# Plaat.net
KiCad netlist of a schematic drawn in EAGLE
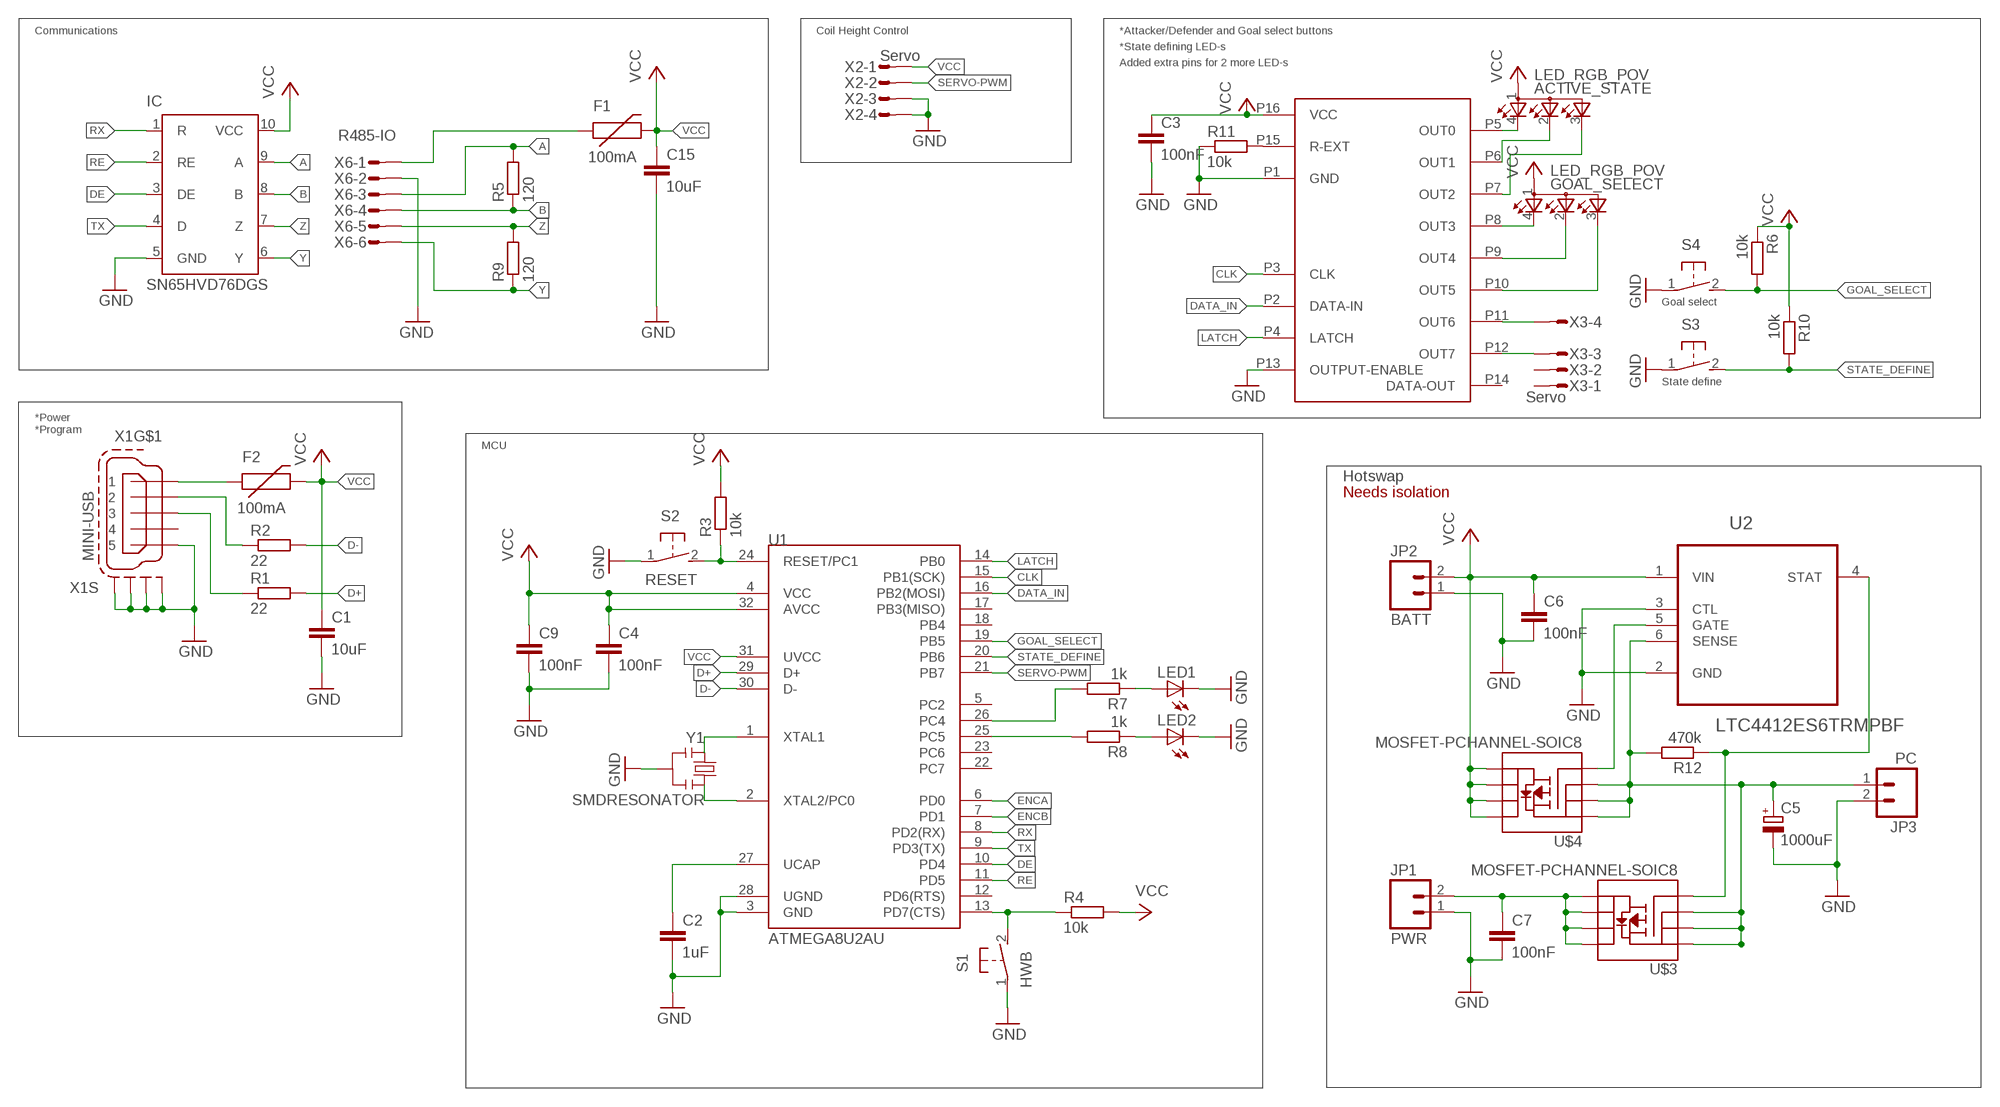
[diagram p0: schematic, sheet 1]

(export (version "E")
  (design (tool "Eeschema 10.0.6"))
  (components
    (comp (ref "ACTIVE_STATE")
      (value "LED_RGB_POV")
      (footprint "eagle-import:P-LCC-4-2")
      (libsource (lib "eagle-import") (part "LED_RGB_POV"))
    )
    (comp (ref "C1")
      (value "10uF")
      (footprint "eagle-import:C1206K")
      (libsource (lib "eagle-import") (part "C-EUC1206K"))
    )
    (comp (ref "C2")
      (value "1uF")
      (footprint "eagle-import:C0603K")
      (libsource (lib "eagle-import") (part "C-EUC0603K"))
    )
    (comp (ref "C3")
      (value "100nF")
      (footprint "eagle-import:C0603K")
      (libsource (lib "eagle-import") (part "C-EUC0603K"))
    )
    (comp (ref "C4")
      (value "100nF")
      (footprint "eagle-import:C0603K")
      (libsource (lib "eagle-import") (part "C-EUC0603K"))
    )
    (comp (ref "C5")
      (value "1000uF")
      (footprint "eagle-import:E3,5-8")
      (libsource (lib "eagle-import") (part "CPOL-EUE3.5-8"))
    )
    (comp (ref "C6")
      (value "100nF")
      (footprint "eagle-import:C0603K")
      (libsource (lib "eagle-import") (part "C-EUC0603K"))
    )
    (comp (ref "C7")
      (value "100nF")
      (footprint "eagle-import:C0603K")
      (libsource (lib "eagle-import") (part "C-EUC0603K"))
    )
    (comp (ref "C9")
      (value "100nF")
      (footprint "eagle-import:C0603K")
      (libsource (lib "eagle-import") (part "C-EUC0603K"))
    )
    (comp (ref "C15")
      (value "10uF")
      (footprint "eagle-import:C1206K")
      (libsource (lib "eagle-import") (part "C-EUC1206K"))
    )
    (comp (ref "F1")
      (value "100mA")
      (footprint "eagle-import:PTC-1206")
      (libsource (lib "eagle-import") (part "PTCSMD"))
    )
    (comp (ref "F2")
      (value "100mA")
      (footprint "eagle-import:PTC-1206")
      (libsource (lib "eagle-import") (part "PTCSMD"))
    )
    (comp (ref "GOAL_SELECT")
      (value "LED_RGB_POV")
      (footprint "eagle-import:P-LCC-4-2")
      (libsource (lib "eagle-import") (part "LED_RGB_POV"))
    )
    (comp (ref "JP1")
      (value "PWR")
      (footprint "eagle-import:SCREWTERMINAL-3.5MM-2")
      (libsource (lib "eagle-import") (part "M023.5MM"))
    )
    (comp (ref "JP2")
      (value "BATT")
      (footprint "eagle-import:SCREWTERMINAL-3.5MM-2")
      (libsource (lib "eagle-import") (part "M023.5MM"))
    )
    (comp (ref "JP3")
      (value "PC")
      (footprint "eagle-import:SCREWTERMINAL-3.5MM-2")
      (libsource (lib "eagle-import") (part "M023.5MM"))
    )
    (comp (ref "LED1")
      (value "LEDCHIP-LED0603")
      (footprint "eagle-import:CHIP-LED0603")
      (libsource (lib "eagle-import") (part "LEDCHIP-LED0603"))
    )
    (comp (ref "LED2")
      (value "LEDCHIP-LED0603")
      (footprint "eagle-import:CHIP-LED0603")
      (libsource (lib "eagle-import") (part "LEDCHIP-LED0603"))
    )
    (comp (ref "R1")
      (value "22")
      (footprint "eagle-import:R0603")
      (libsource (lib "eagle-import") (part "R-EU_R0603"))
    )
    (comp (ref "R2")
      (value "22")
      (footprint "eagle-import:R0603")
      (libsource (lib "eagle-import") (part "R-EU_R0603"))
    )
    (comp (ref "R3")
      (value "10k")
      (footprint "eagle-import:R0603")
      (libsource (lib "eagle-import") (part "R-EU_R0603"))
    )
    (comp (ref "R4")
      (value "10k")
      (footprint "eagle-import:R0603")
      (libsource (lib "eagle-import") (part "R-EU_R0603"))
    )
    (comp (ref "R5")
      (value "120")
      (footprint "eagle-import:R0603")
      (libsource (lib "eagle-import") (part "R-EU_R0603"))
    )
    (comp (ref "R6")
      (value "10k")
      (footprint "eagle-import:R0603")
      (libsource (lib "eagle-import") (part "R-EU_R0603"))
    )
    (comp (ref "R7")
      (value "1k")
      (footprint "eagle-import:R0603")
      (libsource (lib "eagle-import") (part "R-EU_R0603"))
    )
    (comp (ref "R8")
      (value "1k")
      (footprint "eagle-import:R0603")
      (libsource (lib "eagle-import") (part "R-EU_R0603"))
    )
    (comp (ref "R9")
      (value "120")
      (footprint "eagle-import:R0603")
      (libsource (lib "eagle-import") (part "R-EU_R0603"))
    )
    (comp (ref "R10")
      (value "10k")
      (footprint "eagle-import:R0603")
      (libsource (lib "eagle-import") (part "R-EU_R0603"))
    )
    (comp (ref "R11")
      (value "10k")
      (footprint "eagle-import:R0603")
      (libsource (lib "eagle-import") (part "R-EU_R0603"))
    )
    (comp (ref "R12")
      (value "470k")
      (footprint "eagle-import:R0603")
      (libsource (lib "eagle-import") (part "R-EU_R0603"))
    )
    (comp (ref "S1")
      (value "HWB")
      (footprint "eagle-import:ADTSM3")
      (libsource (lib "eagle-import") (part "ADTSM3"))
    )
    (comp (ref "S2")
      (value "RESET")
      (footprint "eagle-import:ADTSM3")
      (libsource (lib "eagle-import") (part "ADTSM3"))
    )
    (comp (ref "S3")
      (value "RESET")
      (footprint "eagle-import:ADTSM3")
      (libsource (lib "eagle-import") (part "ADTSM3"))
    )
    (comp (ref "S4")
      (value "RESET")
      (footprint "eagle-import:ADTSM3")
      (libsource (lib "eagle-import") (part "ADTSM3"))
    )
    (comp (ref "U$1")
      (value "SN65HVF76DGS")
      (footprint "eagle-import:MSOP10")
      (libsource (lib "eagle-import") (part "SN65HVF76DGS"))
    )
    (comp (ref "U$2")
      (value "STP08DP05")
      (footprint "eagle-import:HTSSOP16")
      (libsource (lib "eagle-import") (part "STP08DP05"))
    )
    (comp (ref "U$3")
      (value "MOSFET-PCHANNEL-SOIC8")
      (footprint "eagle-import:SO08")
      (libsource (lib "eagle-import") (part "MOSFET-PCHANNEL-SOIC8SOIC8"))
    )
    (comp (ref "U$4")
      (value "MOSFET-PCHANNEL-SOIC8")
      (footprint "eagle-import:SO08")
      (libsource (lib "eagle-import") (part "MOSFET-PCHANNEL-SOIC8SOIC8"))
    )
    (comp (ref "U1")
      (value "ATMEGA8U2AU")
      (footprint "eagle-import:TQFP32-08")
      (libsource (lib "eagle-import") (part "ATMEGA8U2AU"))
    )
    (comp (ref "U2")
      (value "LTC4412ES6TRMPBF")
      (footprint "eagle-import:SOT95P280X100-6N")
      (fields (field (name "MPN") "LTC4412ES6#TRMPBF"))
      (libsource (lib "eagle-import") (part "LTC4412ES6TRMPBF"))
    )
    (comp (ref "X1")
      (value "MINI-USB")
      (footprint "eagle-import:32005-301")
      (libsource (lib "eagle-import") (part "MINI-USB-SCHIELD-32005-301"))
    )
    (comp (ref "X2")
      (value "Servo")
      (footprint "eagle-import:MICROMATCH-4")
      (fields (field (name "MPN") "7-215464-4"))
      (libsource (lib "eagle-import") (part "MICROMATCH-4"))
    )
    (comp (ref "X3")
      (value "Servo")
      (footprint "eagle-import:MICROMATCH-4")
      (fields (field (name "MPN") "7-215464-4"))
      (libsource (lib "eagle-import") (part "MICROMATCH-4"))
    )
    (comp (ref "X6")
      (value "R485-IO")
      (footprint "eagle-import:MICROMATCH-6")
      (fields (field (name "MPN") "7-215464-6"))
      (libsource (lib "eagle-import") (part "MICROMATCH-6"))
    )
    (comp (ref "Y1")
      (value "SMDRESONATOR")
      (footprint "eagle-import:PBRC-M")
      (libsource (lib "eagle-import") (part "SMDRESONATOR45X20"))
    )
  )
  (nets
    (net (code "1") (name "A") (class "Default")
      (node (ref "R5") (pin "2") (pinfunction "2_2") (pintype "passive"))
      (node (ref "U$1") (pin "9") (pinfunction "A_9") (pintype "input"))
      (node (ref "X6") (pin "3") (pinfunction "S_3") (pintype "passive"))
    )
    (net (code "2") (name "B") (class "Default")
      (node (ref "R5") (pin "1") (pinfunction "1_1") (pintype "passive"))
      (node (ref "U$1") (pin "8") (pinfunction "B_8") (pintype "input"))
      (node (ref "X6") (pin "4") (pinfunction "S_4") (pintype "passive"))
    )
    (net (code "3") (name "CLK") (class "Default")
      (node (ref "U$2") (pin "P3") (pinfunction "CLK_P3") (pintype "bidirectional"))
      (node (ref "U1") (pin "15") (pinfunction "PB1(SCK)_15") (pintype "bidirectional"))
    )
    (net (code "4") (name "D+") (class "Default")
      (node (ref "R1") (pin "2") (pinfunction "2_2") (pintype "passive"))
      (node (ref "U1") (pin "29") (pinfunction "D+_29") (pintype "bidirectional"))
    )
    (net (code "5") (name "D-") (class "Default")
      (node (ref "R2") (pin "2") (pinfunction "2_2") (pintype "passive"))
      (node (ref "U1") (pin "30") (pinfunction "D-_30") (pintype "bidirectional"))
    )
    (net (code "6") (name "DATA_IN") (class "Default")
      (node (ref "U$2") (pin "P2") (pinfunction "DATA-IN_P2") (pintype "bidirectional"))
      (node (ref "U1") (pin "16") (pinfunction "PB2(MOSI)_16") (pintype "bidirectional"))
    )
    (net (code "7") (name "DE") (class "Default")
      (node (ref "U$1") (pin "3") (pinfunction "DE_3") (pintype "input"))
      (node (ref "U1") (pin "10") (pinfunction "PD4_10") (pintype "bidirectional"))
    )
    (net (code "8") (name "ENCA") (class "Default")
      (node (ref "U1") (pin "6") (pinfunction "PD0_6") (pintype "bidirectional"))
    )
    (net (code "9") (name "ENCB") (class "Default")
      (node (ref "U1") (pin "7") (pinfunction "PD1_7") (pintype "bidirectional"))
    )
    (net (code "10") (name "GND") (class "Default")
      (node (ref "C1") (pin "2") (pinfunction "2_2") (pintype "passive"))
      (node (ref "C15") (pin "2") (pinfunction "2_2") (pintype "passive"))
      (node (ref "C2") (pin "2") (pinfunction "2_2") (pintype "passive"))
      (node (ref "C3") (pin "2") (pinfunction "2_2") (pintype "passive"))
      (node (ref "C4") (pin "2") (pinfunction "2_2") (pintype "passive"))
      (node (ref "C5") (pin "-") (pinfunction "-_-") (pintype "passive"))
      (node (ref "C6") (pin "2") (pinfunction "2_2") (pintype "passive"))
      (node (ref "C7") (pin "2") (pinfunction "2_2") (pintype "passive"))
      (node (ref "C9") (pin "2") (pinfunction "2_2") (pintype "passive"))
      (node (ref "JP1") (pin "1") (pinfunction "1_1") (pintype "passive"))
      (node (ref "JP2") (pin "1") (pinfunction "1_1") (pintype "passive"))
      (node (ref "JP3") (pin "2") (pinfunction "2_2") (pintype "passive"))
      (node (ref "LED1") (pin "C") (pinfunction "C_C") (pintype "passive"))
      (node (ref "LED2") (pin "C") (pinfunction "C_C") (pintype "passive"))
      (node (ref "R11") (pin "1") (pinfunction "1_1") (pintype "passive"))
      (node (ref "S1") (pin "1") (pinfunction "1_1") (pintype "passive"))
      (node (ref "S2") (pin "1") (pinfunction "1_1") (pintype "passive"))
      (node (ref "S3") (pin "1") (pinfunction "1_1") (pintype "passive"))
      (node (ref "S4") (pin "1") (pinfunction "1_1") (pintype "passive"))
      (node (ref "U$1") (pin "5") (pinfunction "GND_5") (pintype "power_in"))
      (node (ref "U$2") (pin "P1") (pinfunction "GND_P1") (pintype "bidirectional"))
      (node (ref "U$2") (pin "P13") (pinfunction "OUTPUT-ENABLE_P13") (pintype "bidirectional"))
      (node (ref "U1") (pin "28") (pinfunction "UGND_28") (pintype "bidirectional"))
      (node (ref "U1") (pin "3") (pinfunction "GND_3") (pintype "bidirectional"))
      (node (ref "U2") (pin "2") (pinfunction "GND_2") (pintype "passive"))
      (node (ref "U2") (pin "3") (pinfunction "CTL_3") (pintype "input"))
      (node (ref "X1") (pin "5") (pinfunction "5_5") (pintype "passive"))
      (node (ref "X1") (pin "M1") (pinfunction "S1_M1") (pintype "passive"))
      (node (ref "X1") (pin "M2") (pinfunction "S2_M2") (pintype "passive"))
      (node (ref "X1") (pin "M3") (pinfunction "S3_M3") (pintype "passive"))
      (node (ref "X1") (pin "M4") (pinfunction "S4_M4") (pintype "passive"))
      (node (ref "X2") (pin "3") (pinfunction "S_3") (pintype "passive"))
      (node (ref "X2") (pin "4") (pinfunction "S_4") (pintype "passive"))
      (node (ref "X6") (pin "2") (pinfunction "S_2") (pintype "passive"))
      (node (ref "Y1") (pin "2") (pinfunction "P$2_2") (pintype "power_in"))
    )
    (net (code "11") (name "GOAL_SELECT") (class "Default")
      (node (ref "R6") (pin "2") (pinfunction "2_2") (pintype "passive"))
      (node (ref "S4") (pin "2") (pinfunction "2_2") (pintype "passive"))
      (node (ref "U1") (pin "19") (pinfunction "PB5_19") (pintype "bidirectional"))
    )
    (net (code "12") (name "LATCH") (class "Default")
      (node (ref "U$2") (pin "P4") (pinfunction "LATCH_P4") (pintype "bidirectional"))
      (node (ref "U1") (pin "14") (pinfunction "PB0_14") (pintype "bidirectional"))
    )
    (net (code "13") (name "Net-(ACTIVE_STATE-CBLUE)") (class "Default")
      (node (ref "ACTIVE_STATE") (pin "2") (pinfunction "CBLUE_2") (pintype "passive"))
      (node (ref "U$2") (pin "P6") (pinfunction "OUT1_P6") (pintype "bidirectional"))
    )
    (net (code "14") (name "Net-(ACTIVE_STATE-CGREEN)") (class "Default")
      (node (ref "ACTIVE_STATE") (pin "3") (pinfunction "CGREEN_3") (pintype "passive"))
      (node (ref "U$2") (pin "P7") (pinfunction "OUT2_P7") (pintype "bidirectional"))
    )
    (net (code "15") (name "Net-(ACTIVE_STATE-CRED)") (class "Default")
      (node (ref "ACTIVE_STATE") (pin "4") (pinfunction "CRED_4") (pintype "passive"))
      (node (ref "U$2") (pin "P5") (pinfunction "OUT0_P5") (pintype "bidirectional"))
    )
    (net (code "16") (name "Net-(C7-Pad1)") (class "Default")
      (node (ref "C7") (pin "1") (pinfunction "1_1") (pintype "passive"))
      (node (ref "JP1") (pin "2") (pinfunction "2_2") (pintype "passive"))
      (node (ref "U$3") (pin "5") (pinfunction "D_5") (pintype "bidirectional"))
      (node (ref "U$3") (pin "6") (pinfunction "D_6") (pintype "bidirectional"))
      (node (ref "U$3") (pin "7") (pinfunction "D_7") (pintype "bidirectional"))
      (node (ref "U$3") (pin "8") (pinfunction "D_8") (pintype "bidirectional"))
    )
    (net (code "17") (name "Net-(F2-Pad1)") (class "Default")
      (node (ref "F2") (pin "1") (pinfunction "1_1") (pintype "bidirectional"))
      (node (ref "X1") (pin "1") (pinfunction "1_1") (pintype "passive"))
    )
    (net (code "18") (name "Net-(GOAL_SELECT-CBLUE)") (class "Default")
      (node (ref "GOAL_SELECT") (pin "2") (pinfunction "CBLUE_2") (pintype "passive"))
      (node (ref "U$2") (pin "P9") (pinfunction "OUT4_P9") (pintype "bidirectional"))
    )
    (net (code "19") (name "Net-(GOAL_SELECT-CGREEN)") (class "Default")
      (node (ref "GOAL_SELECT") (pin "3") (pinfunction "CGREEN_3") (pintype "passive"))
      (node (ref "U$2") (pin "P10") (pinfunction "OUT5_P10") (pintype "bidirectional"))
    )
    (net (code "20") (name "Net-(GOAL_SELECT-CRED)") (class "Default")
      (node (ref "GOAL_SELECT") (pin "4") (pinfunction "CRED_4") (pintype "passive"))
      (node (ref "U$2") (pin "P8") (pinfunction "OUT3_P8") (pintype "bidirectional"))
    )
    (net (code "21") (name "Net-(LED1-PadA)") (class "Default")
      (node (ref "LED1") (pin "A") (pinfunction "A_A") (pintype "passive"))
      (node (ref "R7") (pin "1") (pinfunction "1_1") (pintype "passive"))
    )
    (net (code "22") (name "Net-(LED2-PadA)") (class "Default")
      (node (ref "LED2") (pin "A") (pinfunction "A_A") (pintype "passive"))
      (node (ref "R8") (pin "1") (pinfunction "1_1") (pintype "passive"))
    )
    (net (code "23") (name "Net-(R1-Pad1)") (class "Default")
      (node (ref "R1") (pin "1") (pinfunction "1_1") (pintype "passive"))
      (node (ref "X1") (pin "3") (pinfunction "3_3") (pintype "passive"))
    )
    (net (code "24") (name "Net-(R2-Pad1)") (class "Default")
      (node (ref "R2") (pin "1") (pinfunction "1_1") (pintype "passive"))
      (node (ref "X1") (pin "2") (pinfunction "2_2") (pintype "passive"))
    )
    (net (code "25") (name "Net-(U$2-OUT6)") (class "Default")
      (node (ref "U$2") (pin "P11") (pinfunction "OUT6_P11") (pintype "bidirectional"))
      (node (ref "X3") (pin "4") (pinfunction "S_4") (pintype "passive"))
    )
    (net (code "26") (name "Net-(U$2-OUT7)") (class "Default")
      (node (ref "U$2") (pin "P12") (pinfunction "OUT7_P12") (pintype "bidirectional"))
      (node (ref "X3") (pin "3") (pinfunction "S_3") (pintype "passive"))
    )
    (net (code "27") (name "Net-(U$2-R-EXT)") (class "Default")
      (node (ref "R11") (pin "2") (pinfunction "2_2") (pintype "passive"))
      (node (ref "U$2") (pin "P15") (pinfunction "R-EXT_P15") (pintype "bidirectional"))
    )
    (net (code "28") (name "Net-(U$3-G)") (class "Default")
      (node (ref "R12") (pin "1") (pinfunction "1_1") (pintype "passive"))
      (node (ref "U$3") (pin "4") (pinfunction "G_4") (pintype "bidirectional"))
      (node (ref "U2") (pin "4") (pinfunction "STAT_4") (pintype "output"))
    )
    (net (code "29") (name "Net-(U$4-G)") (class "Default")
      (node (ref "U$4") (pin "4") (pinfunction "G_4") (pintype "bidirectional"))
      (node (ref "U2") (pin "5") (pinfunction "GATE_5") (pintype "input"))
    )
    (net (code "30") (name "Net-(U1-PC4)") (class "Default")
      (node (ref "R7") (pin "2") (pinfunction "2_2") (pintype "passive"))
      (node (ref "U1") (pin "26") (pinfunction "PC4_26") (pintype "bidirectional"))
    )
    (net (code "31") (name "Net-(U1-PC5)") (class "Default")
      (node (ref "R8") (pin "2") (pinfunction "2_2") (pintype "passive"))
      (node (ref "U1") (pin "25") (pinfunction "PC5_25") (pintype "bidirectional"))
    )
    (net (code "32") (name "Net-(U1-PD7(CTS))") (class "Default")
      (node (ref "R4") (pin "1") (pinfunction "1_1") (pintype "passive"))
      (node (ref "S1") (pin "2") (pinfunction "2_2") (pintype "passive"))
      (node (ref "U1") (pin "13") (pinfunction "PD7(CTS)_13") (pintype "bidirectional"))
    )
    (net (code "33") (name "Net-(U1-RESET{slash}PC1)") (class "Default")
      (node (ref "R3") (pin "1") (pinfunction "1_1") (pintype "passive"))
      (node (ref "S2") (pin "2") (pinfunction "2_2") (pintype "passive"))
      (node (ref "U1") (pin "24") (pinfunction "RESET/PC1_24") (pintype "bidirectional"))
    )
    (net (code "34") (name "Net-(U1-UCAP)") (class "Default")
      (node (ref "C2") (pin "1") (pinfunction "1_1") (pintype "passive"))
      (node (ref "U1") (pin "27") (pinfunction "UCAP_27") (pintype "bidirectional"))
    )
    (net (code "35") (name "Net-(U1-XTAL1)") (class "Default")
      (node (ref "U1") (pin "1") (pinfunction "XTAL1_1") (pintype "bidirectional"))
      (node (ref "Y1") (pin "1") (pinfunction "P$1_1") (pintype "bidirectional"))
    )
    (net (code "36") (name "Net-(U1-XTAL2{slash}PC0)") (class "Default")
      (node (ref "U1") (pin "2") (pinfunction "XTAL2/PC0_2") (pintype "bidirectional"))
      (node (ref "Y1") (pin "3") (pinfunction "P$3_3") (pintype "bidirectional"))
    )
    (net (code "37") (name "Net-(U2-SENSE)") (class "Default")
      (node (ref "C5") (pin "+") (pinfunction "+_+") (pintype "passive"))
      (node (ref "JP3") (pin "1") (pinfunction "1_1") (pintype "passive"))
      (node (ref "R12") (pin "2") (pinfunction "2_2") (pintype "passive"))
      (node (ref "U$3") (pin "1") (pinfunction "S_1") (pintype "bidirectional"))
      (node (ref "U$3") (pin "2") (pinfunction "S_2") (pintype "bidirectional"))
      (node (ref "U$3") (pin "3") (pinfunction "S_3") (pintype "bidirectional"))
      (node (ref "U$4") (pin "1") (pinfunction "S_1") (pintype "bidirectional"))
      (node (ref "U$4") (pin "2") (pinfunction "S_2") (pintype "bidirectional"))
      (node (ref "U$4") (pin "3") (pinfunction "S_3") (pintype "bidirectional"))
      (node (ref "U2") (pin "6") (pinfunction "SENSE_6") (pintype "input"))
    )
    (net (code "38") (name "Net-(X6A-S)") (class "Default")
      (node (ref "F1") (pin "1") (pinfunction "1_1") (pintype "bidirectional"))
      (node (ref "X6") (pin "1") (pinfunction "S_1") (pintype "passive"))
    )
    (net (code "39") (name "RE") (class "Default")
      (node (ref "U$1") (pin "2") (pinfunction "RE_2") (pintype "input"))
      (node (ref "U1") (pin "11") (pinfunction "PD5_11") (pintype "bidirectional"))
    )
    (net (code "40") (name "RX") (class "Default")
      (node (ref "U$1") (pin "1") (pinfunction "R_1") (pintype "output"))
      (node (ref "U1") (pin "8") (pinfunction "PD2(RX)_8") (pintype "bidirectional"))
    )
    (net (code "41") (name "SERVO-PWM") (class "Default")
      (node (ref "U1") (pin "21") (pinfunction "PB7_21") (pintype "bidirectional"))
      (node (ref "X2") (pin "2") (pinfunction "S_2") (pintype "passive"))
    )
    (net (code "42") (name "STATE_DEFINE") (class "Default")
      (node (ref "R10") (pin "2") (pinfunction "2_2") (pintype "passive"))
      (node (ref "S3") (pin "2") (pinfunction "2_2") (pintype "passive"))
      (node (ref "U1") (pin "20") (pinfunction "PB6_20") (pintype "bidirectional"))
    )
    (net (code "43") (name "TX") (class "Default")
      (node (ref "U$1") (pin "4") (pinfunction "D_4") (pintype "input"))
      (node (ref "U1") (pin "9") (pinfunction "PD3(TX)_9") (pintype "bidirectional"))
    )
    (net (code "44") (name "VCC") (class "Default")
      (node (ref "ACTIVE_STATE") (pin "1") (pinfunction "A_1") (pintype "passive"))
      (node (ref "C1") (pin "1") (pinfunction "1_1") (pintype "passive"))
      (node (ref "C15") (pin "1") (pinfunction "1_1") (pintype "passive"))
      (node (ref "C3") (pin "1") (pinfunction "1_1") (pintype "passive"))
      (node (ref "C4") (pin "1") (pinfunction "1_1") (pintype "passive"))
      (node (ref "C6") (pin "1") (pinfunction "1_1") (pintype "passive"))
      (node (ref "C9") (pin "1") (pinfunction "1_1") (pintype "passive"))
      (node (ref "F1") (pin "2") (pinfunction "2_2") (pintype "bidirectional"))
      (node (ref "F2") (pin "2") (pinfunction "2_2") (pintype "bidirectional"))
      (node (ref "GOAL_SELECT") (pin "1") (pinfunction "A_1") (pintype "passive"))
      (node (ref "JP2") (pin "2") (pinfunction "2_2") (pintype "passive"))
      (node (ref "R10") (pin "1") (pinfunction "1_1") (pintype "passive"))
      (node (ref "R3") (pin "2") (pinfunction "2_2") (pintype "passive"))
      (node (ref "R4") (pin "2") (pinfunction "2_2") (pintype "passive"))
      (node (ref "R6") (pin "1") (pinfunction "1_1") (pintype "passive"))
      (node (ref "U$1") (pin "10") (pinfunction "VCC_10") (pintype "input"))
      (node (ref "U$2") (pin "P16") (pinfunction "VCC_P16") (pintype "bidirectional"))
      (node (ref "U$4") (pin "5") (pinfunction "D_5") (pintype "bidirectional"))
      (node (ref "U$4") (pin "6") (pinfunction "D_6") (pintype "bidirectional"))
      (node (ref "U$4") (pin "7") (pinfunction "D_7") (pintype "bidirectional"))
      (node (ref "U$4") (pin "8") (pinfunction "D_8") (pintype "bidirectional"))
      (node (ref "U1") (pin "31") (pinfunction "UVCC_31") (pintype "bidirectional"))
      (node (ref "U1") (pin "32") (pinfunction "AVCC_32") (pintype "bidirectional"))
      (node (ref "U1") (pin "4") (pinfunction "VCC_4") (pintype "bidirectional"))
      (node (ref "U2") (pin "1") (pinfunction "VIN_1") (pintype "power_in"))
      (node (ref "X2") (pin "1") (pinfunction "S_1") (pintype "passive"))
    )
    (net (code "45") (name "Y") (class "Default")
      (node (ref "R9") (pin "1") (pinfunction "1_1") (pintype "passive"))
      (node (ref "U$1") (pin "6") (pinfunction "Y_6") (pintype "output"))
      (node (ref "X6") (pin "6") (pinfunction "S_6") (pintype "passive"))
    )
    (net (code "46") (name "Z") (class "Default")
      (node (ref "R9") (pin "2") (pinfunction "2_2") (pintype "passive"))
      (node (ref "U$1") (pin "7") (pinfunction "Z_7") (pintype "output"))
      (node (ref "X6") (pin "5") (pinfunction "S_5") (pintype "passive"))
    )
    (net (code "47") (name "unconnected-(U$2-DATA-OUT-PadP14)") (class "Default")
      (node (ref "U$2") (pin "P14") (pinfunction "DATA-OUT_P14") (pintype "bidirectional"))
    )
    (net (code "48") (name "unconnected-(U1-PB3(MISO)-Pad17)") (class "Default")
      (node (ref "U1") (pin "17") (pinfunction "PB3(MISO)_17") (pintype "bidirectional"))
    )
    (net (code "49") (name "unconnected-(U1-PB4-Pad18)") (class "Default")
      (node (ref "U1") (pin "18") (pinfunction "PB4_18") (pintype "bidirectional"))
    )
    (net (code "50") (name "unconnected-(U1-PC2-Pad5)") (class "Default")
      (node (ref "U1") (pin "5") (pinfunction "PC2_5") (pintype "bidirectional"))
    )
    (net (code "51") (name "unconnected-(U1-PC6-Pad23)") (class "Default")
      (node (ref "U1") (pin "23") (pinfunction "PC6_23") (pintype "bidirectional"))
    )
    (net (code "52") (name "unconnected-(U1-PC7-Pad22)") (class "Default")
      (node (ref "U1") (pin "22") (pinfunction "PC7_22") (pintype "bidirectional"))
    )
    (net (code "53") (name "unconnected-(U1-PD6(RTS)-Pad12)") (class "Default")
      (node (ref "U1") (pin "12") (pinfunction "PD6(RTS)_12") (pintype "bidirectional"))
    )
    (net (code "54") (name "unconnected-(X1-Pad4)") (class "Default")
      (node (ref "X1") (pin "4") (pinfunction "4_4") (pintype "passive"))
    )
    (net (code "55") (name "unconnected-(X3A-S-Pad1)") (class "Default")
      (node (ref "X3") (pin "1") (pinfunction "S_1") (pintype "passive"))
    )
    (net (code "56") (name "unconnected-(X3B-S-Pad2)") (class "Default")
      (node (ref "X3") (pin "2") (pinfunction "S_2") (pintype "passive"))
    )
  )
)
